# IRRx.net
KiCad netlist of a schematic drawn in EAGLE
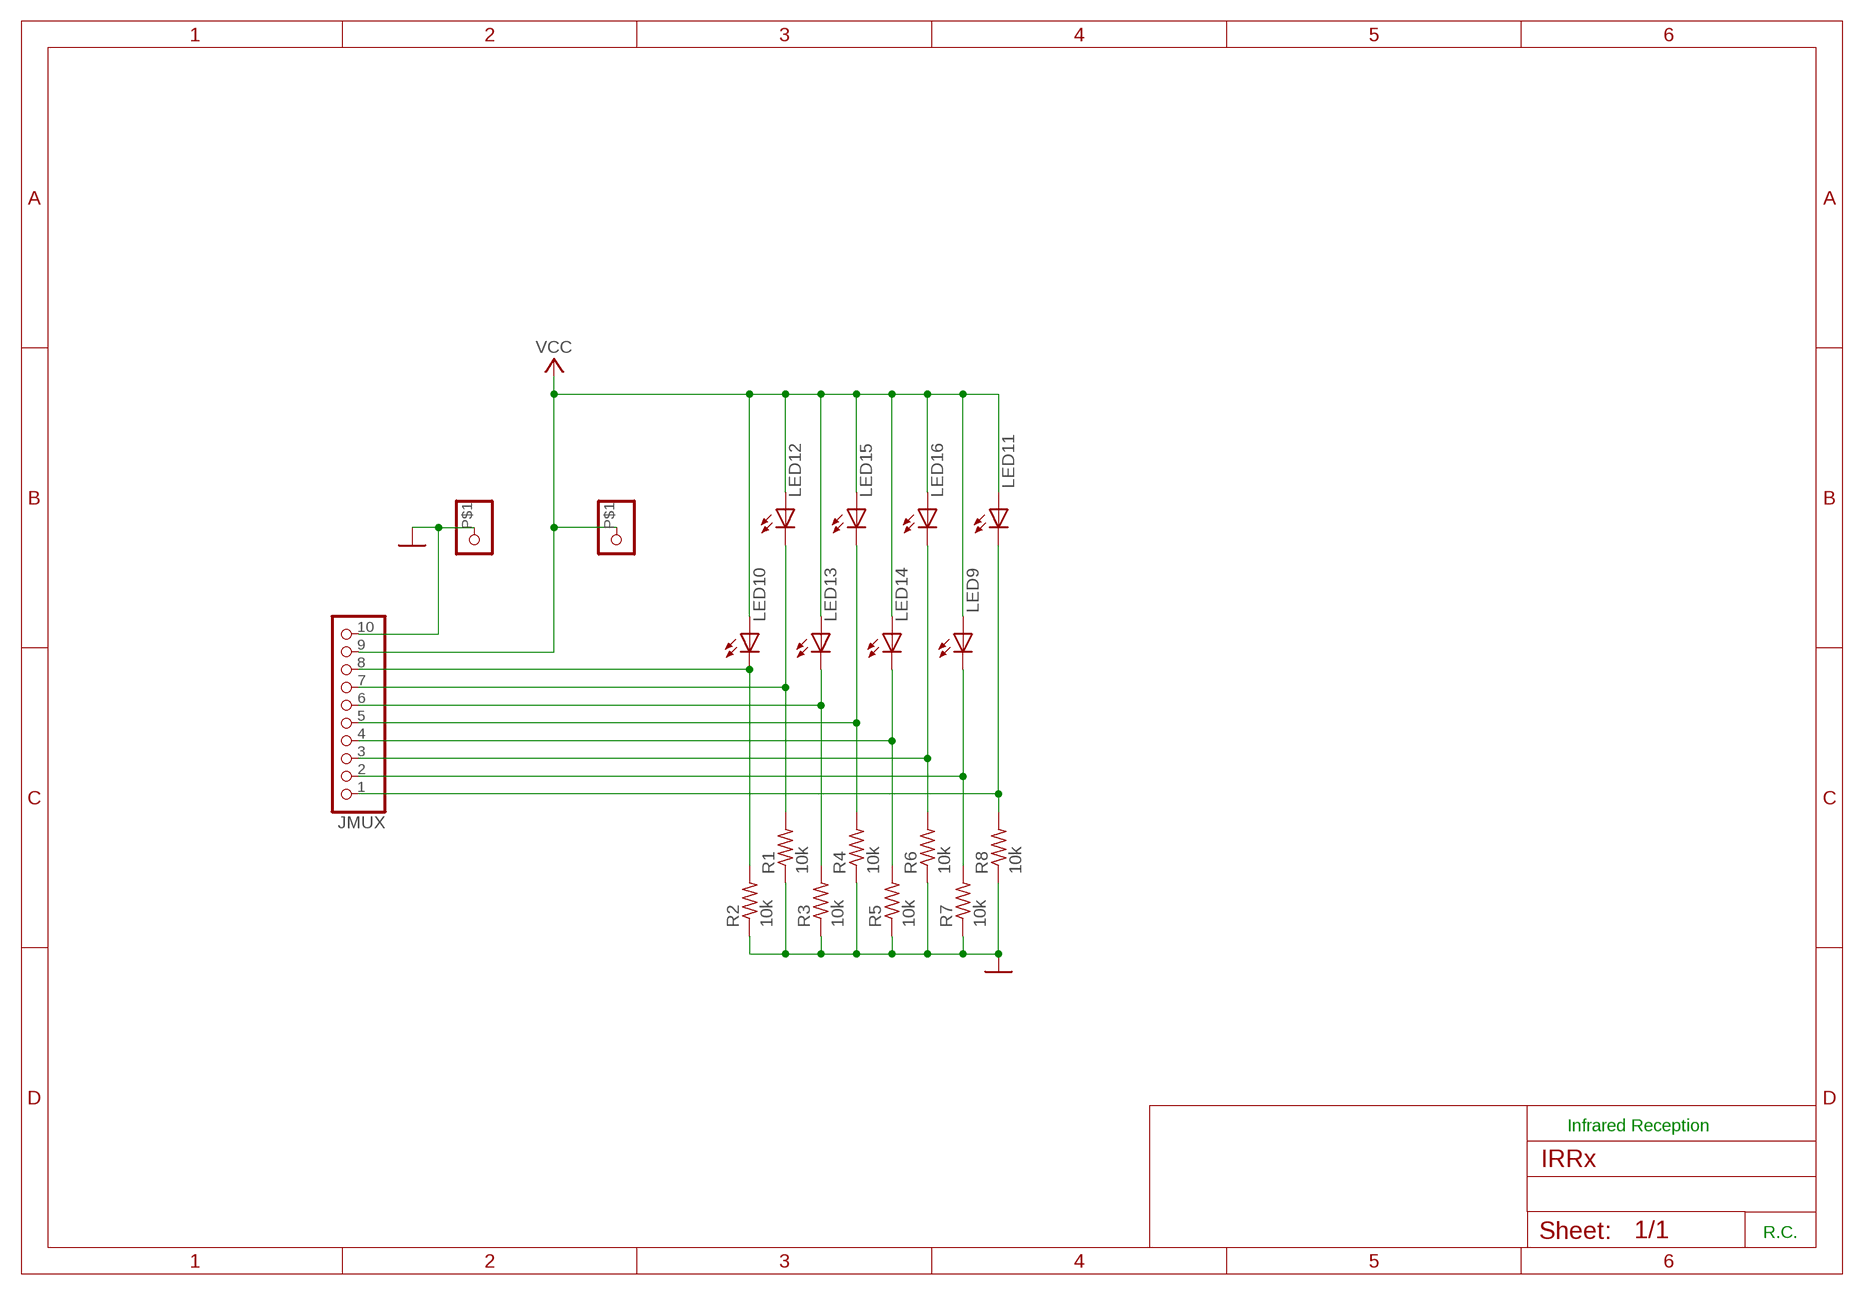
[diagram p0: schematic, sheet 1]

(export (version "E")
  (design (tool "Eeschema 10.0.6"))
  (components
    (comp (ref "JMUX")
      (value "PINHD-1X10")
      (footprint "eagle-import:1X10-BIG")
      (libsource (lib "eagle-import") (part "PINHD-1X10"))
    )
    (comp (ref "JP1")
      (value "3.3")
      (footprint "eagle-import:1X1-BIGPOGO")
      (libsource (lib "eagle-import") (part "PINHD-1X1-BIGPOGO"))
    )
    (comp (ref "JP2")
      (value "GND")
      (footprint "eagle-import:1X1-BIGPOGO")
      (libsource (lib "eagle-import") (part "PINHD-1X1-BIGPOGO"))
    )
    (comp (ref "LED9")
      (value "LED5MM")
      (footprint "eagle-import:LED5MM")
      (libsource (lib "eagle-import") (part "LED5MM"))
    )
    (comp (ref "LED10")
      (value "LED5MM")
      (footprint "eagle-import:LED5MM")
      (libsource (lib "eagle-import") (part "LED5MM"))
    )
    (comp (ref "LED11")
      (value "LED5MM")
      (footprint "eagle-import:LED5MM")
      (libsource (lib "eagle-import") (part "LED5MM"))
    )
    (comp (ref "LED12")
      (value "LED5MM")
      (footprint "eagle-import:LED5MM")
      (libsource (lib "eagle-import") (part "LED5MM"))
    )
    (comp (ref "LED13")
      (value "LED5MM")
      (footprint "eagle-import:LED5MM")
      (libsource (lib "eagle-import") (part "LED5MM"))
    )
    (comp (ref "LED14")
      (value "LED5MM")
      (footprint "eagle-import:LED5MM")
      (libsource (lib "eagle-import") (part "LED5MM"))
    )
    (comp (ref "LED15")
      (value "LED5MM")
      (footprint "eagle-import:LED5MM")
      (libsource (lib "eagle-import") (part "LED5MM"))
    )
    (comp (ref "LED16")
      (value "LED5MM")
      (footprint "eagle-import:LED5MM")
      (libsource (lib "eagle-import") (part "LED5MM"))
    )
    (comp (ref "R1")
      (value "10k")
      (footprint "eagle-import:0207_10")
      (libsource (lib "eagle-import") (part "R-US_0207/10"))
    )
    (comp (ref "R2")
      (value "10k")
      (footprint "eagle-import:0207_10")
      (libsource (lib "eagle-import") (part "R-US_0207/10"))
    )
    (comp (ref "R3")
      (value "10k")
      (footprint "eagle-import:0207_10")
      (libsource (lib "eagle-import") (part "R-US_0207/10"))
    )
    (comp (ref "R4")
      (value "10k")
      (footprint "eagle-import:0207_10")
      (libsource (lib "eagle-import") (part "R-US_0207/10"))
    )
    (comp (ref "R5")
      (value "10k")
      (footprint "eagle-import:0207_10")
      (libsource (lib "eagle-import") (part "R-US_0207/10"))
    )
    (comp (ref "R6")
      (value "10k")
      (footprint "eagle-import:0207_10")
      (libsource (lib "eagle-import") (part "R-US_0207/10"))
    )
    (comp (ref "R7")
      (value "10k")
      (footprint "eagle-import:0207_10")
      (libsource (lib "eagle-import") (part "R-US_0207/10"))
    )
    (comp (ref "R8")
      (value "10k")
      (footprint "eagle-import:0207_10")
      (libsource (lib "eagle-import") (part "R-US_0207/10"))
    )
  )
  (nets
    (net (code "1") (name "GND") (class "Default")
      (node (ref "JMUX") (pin "10") (pinfunction "10_10") (pintype "passive"))
      (node (ref "JP2") (pin "P$1") (pinfunction "1_P$1") (pintype "passive"))
      (node (ref "R1") (pin "1") (pinfunction "1_1") (pintype "passive"))
      (node (ref "R2") (pin "1") (pinfunction "1_1") (pintype "passive"))
      (node (ref "R3") (pin "1") (pinfunction "1_1") (pintype "passive"))
      (node (ref "R4") (pin "1") (pinfunction "1_1") (pintype "passive"))
      (node (ref "R5") (pin "1") (pinfunction "1_1") (pintype "passive"))
      (node (ref "R6") (pin "1") (pinfunction "1_1") (pintype "passive"))
      (node (ref "R7") (pin "1") (pinfunction "1_1") (pintype "passive"))
      (node (ref "R8") (pin "1") (pinfunction "1_1") (pintype "passive"))
    )
    (net (code "2") (name "Net-(LED9-C)") (class "Default")
      (node (ref "JMUX") (pin "2") (pinfunction "2_2") (pintype "passive"))
      (node (ref "LED9") (pin "K") (pinfunction "C_K") (pintype "passive"))
      (node (ref "R7") (pin "2") (pinfunction "2_2") (pintype "passive"))
    )
    (net (code "3") (name "Net-(LED10-C)") (class "Default")
      (node (ref "JMUX") (pin "8") (pinfunction "8_8") (pintype "passive"))
      (node (ref "LED10") (pin "K") (pinfunction "C_K") (pintype "passive"))
      (node (ref "R2") (pin "2") (pinfunction "2_2") (pintype "passive"))
    )
    (net (code "4") (name "Net-(LED11-C)") (class "Default")
      (node (ref "JMUX") (pin "1") (pinfunction "1_1") (pintype "passive"))
      (node (ref "LED11") (pin "K") (pinfunction "C_K") (pintype "passive"))
      (node (ref "R8") (pin "2") (pinfunction "2_2") (pintype "passive"))
    )
    (net (code "5") (name "Net-(LED12-C)") (class "Default")
      (node (ref "JMUX") (pin "7") (pinfunction "7_7") (pintype "passive"))
      (node (ref "LED12") (pin "K") (pinfunction "C_K") (pintype "passive"))
      (node (ref "R1") (pin "2") (pinfunction "2_2") (pintype "passive"))
    )
    (net (code "6") (name "Net-(LED13-C)") (class "Default")
      (node (ref "JMUX") (pin "6") (pinfunction "6_6") (pintype "passive"))
      (node (ref "LED13") (pin "K") (pinfunction "C_K") (pintype "passive"))
      (node (ref "R3") (pin "2") (pinfunction "2_2") (pintype "passive"))
    )
    (net (code "7") (name "Net-(LED14-C)") (class "Default")
      (node (ref "JMUX") (pin "4") (pinfunction "4_4") (pintype "passive"))
      (node (ref "LED14") (pin "K") (pinfunction "C_K") (pintype "passive"))
      (node (ref "R5") (pin "2") (pinfunction "2_2") (pintype "passive"))
    )
    (net (code "8") (name "Net-(LED15-C)") (class "Default")
      (node (ref "JMUX") (pin "5") (pinfunction "5_5") (pintype "passive"))
      (node (ref "LED15") (pin "K") (pinfunction "C_K") (pintype "passive"))
      (node (ref "R4") (pin "2") (pinfunction "2_2") (pintype "passive"))
    )
    (net (code "9") (name "Net-(LED16-C)") (class "Default")
      (node (ref "JMUX") (pin "3") (pinfunction "3_3") (pintype "passive"))
      (node (ref "LED16") (pin "K") (pinfunction "C_K") (pintype "passive"))
      (node (ref "R6") (pin "2") (pinfunction "2_2") (pintype "passive"))
    )
    (net (code "10") (name "VCC") (class "Default")
      (node (ref "JMUX") (pin "9") (pinfunction "9_9") (pintype "passive"))
      (node (ref "JP1") (pin "P$1") (pinfunction "1_P$1") (pintype "passive"))
      (node (ref "LED10") (pin "A") (pinfunction "A_A") (pintype "passive"))
      (node (ref "LED11") (pin "A") (pinfunction "A_A") (pintype "passive"))
      (node (ref "LED12") (pin "A") (pinfunction "A_A") (pintype "passive"))
      (node (ref "LED13") (pin "A") (pinfunction "A_A") (pintype "passive"))
      (node (ref "LED14") (pin "A") (pinfunction "A_A") (pintype "passive"))
      (node (ref "LED15") (pin "A") (pinfunction "A_A") (pintype "passive"))
      (node (ref "LED16") (pin "A") (pinfunction "A_A") (pintype "passive"))
      (node (ref "LED9") (pin "A") (pinfunction "A_A") (pintype "passive"))
    )
  )
)
